# 07_ADC.net
KiCad netlist of a schematic drawn in Altium Designer
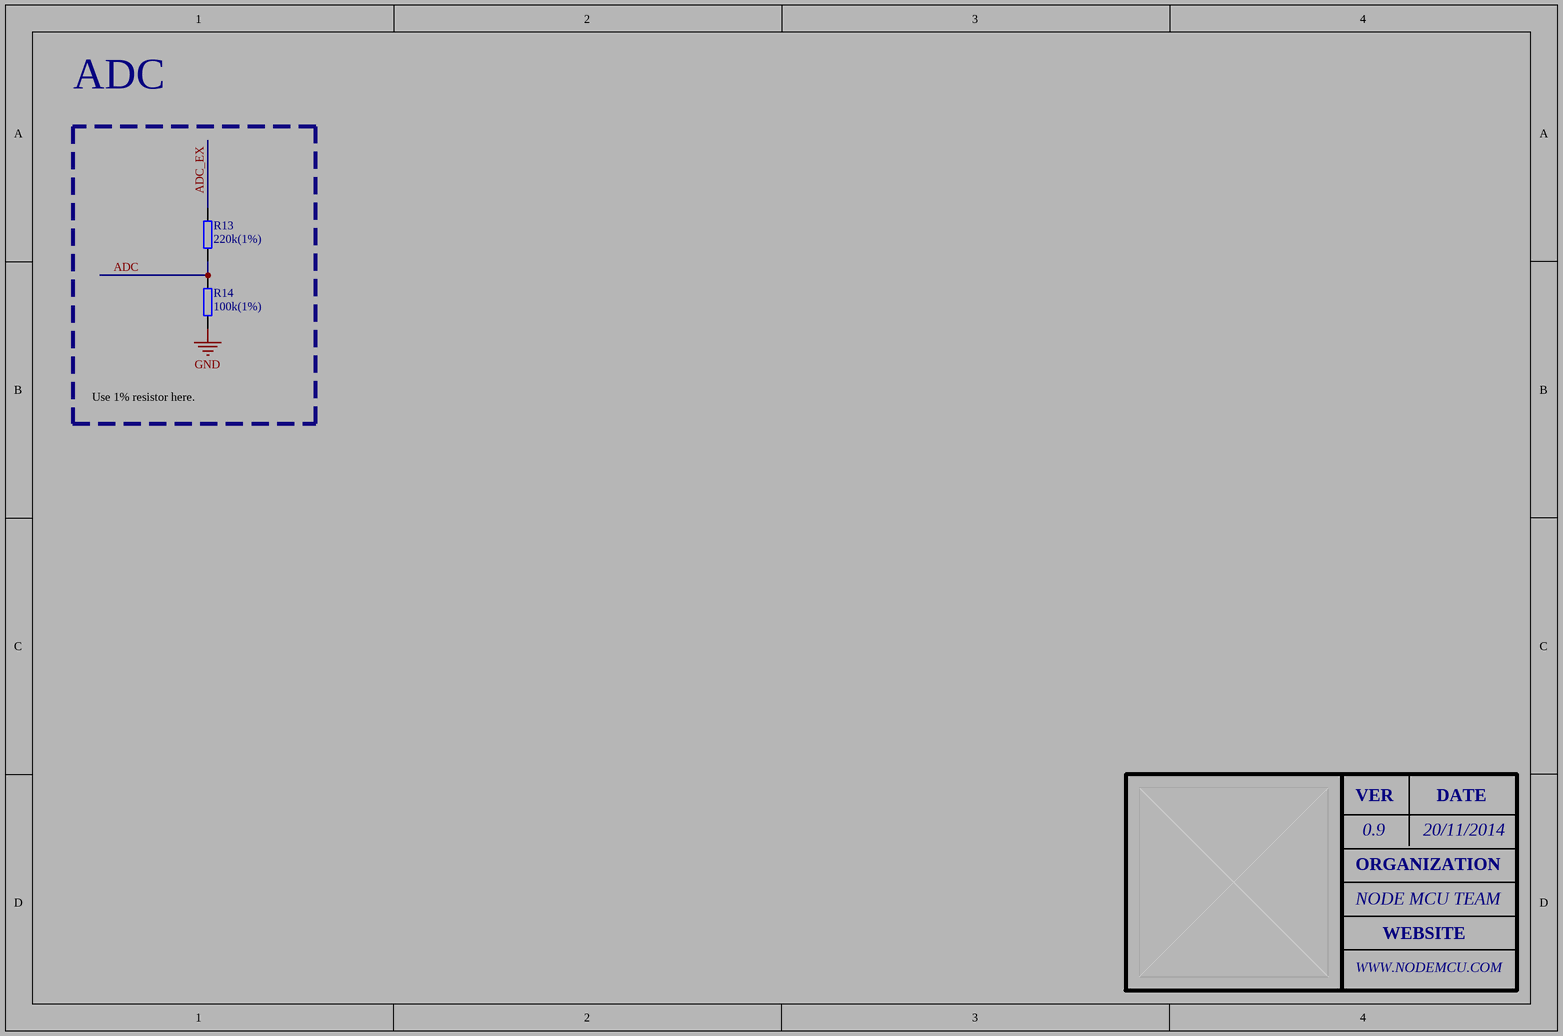
[diagram p0: 07_ADC.SchDoc]

(export (version "E")
  (design (tool "Eeschema 10.0.6"))
  (components
    (comp (ref "R13")
      (value "220k(1%)")
      (footprint "SMT_R_0402")
      (description "Surface mount resistor 0402")
      (libsource (lib "Vowstar_Basic_Device") (part "SMT_R_0402"))
    )
    (comp (ref "R14")
      (value "100k(1%)")
      (footprint "SMT_R_0402")
      (description "Surface mount resistor 0402")
      (libsource (lib "Vowstar_Basic_Device") (part "SMT_R_0402"))
    )
  )
  (nets
    (net (code "1") (name "/ADC") (class "Default")
      (node (ref "R13") (pin "1") (pinfunction "1_1") (pintype "passive"))
      (node (ref "R14") (pin "2") (pinfunction "2_2") (pintype "passive"))
    )
    (net (code "2") (name "/ADC_EX") (class "Default")
      (node (ref "R13") (pin "2") (pinfunction "2_2") (pintype "passive"))
    )
    (net (code "3") (name "GND") (class "Default")
      (node (ref "R14") (pin "1") (pinfunction "1_1") (pintype "passive"))
    )
  )
)
